# uno.net
KiCad netlist of a schematic drawn in EAGLE
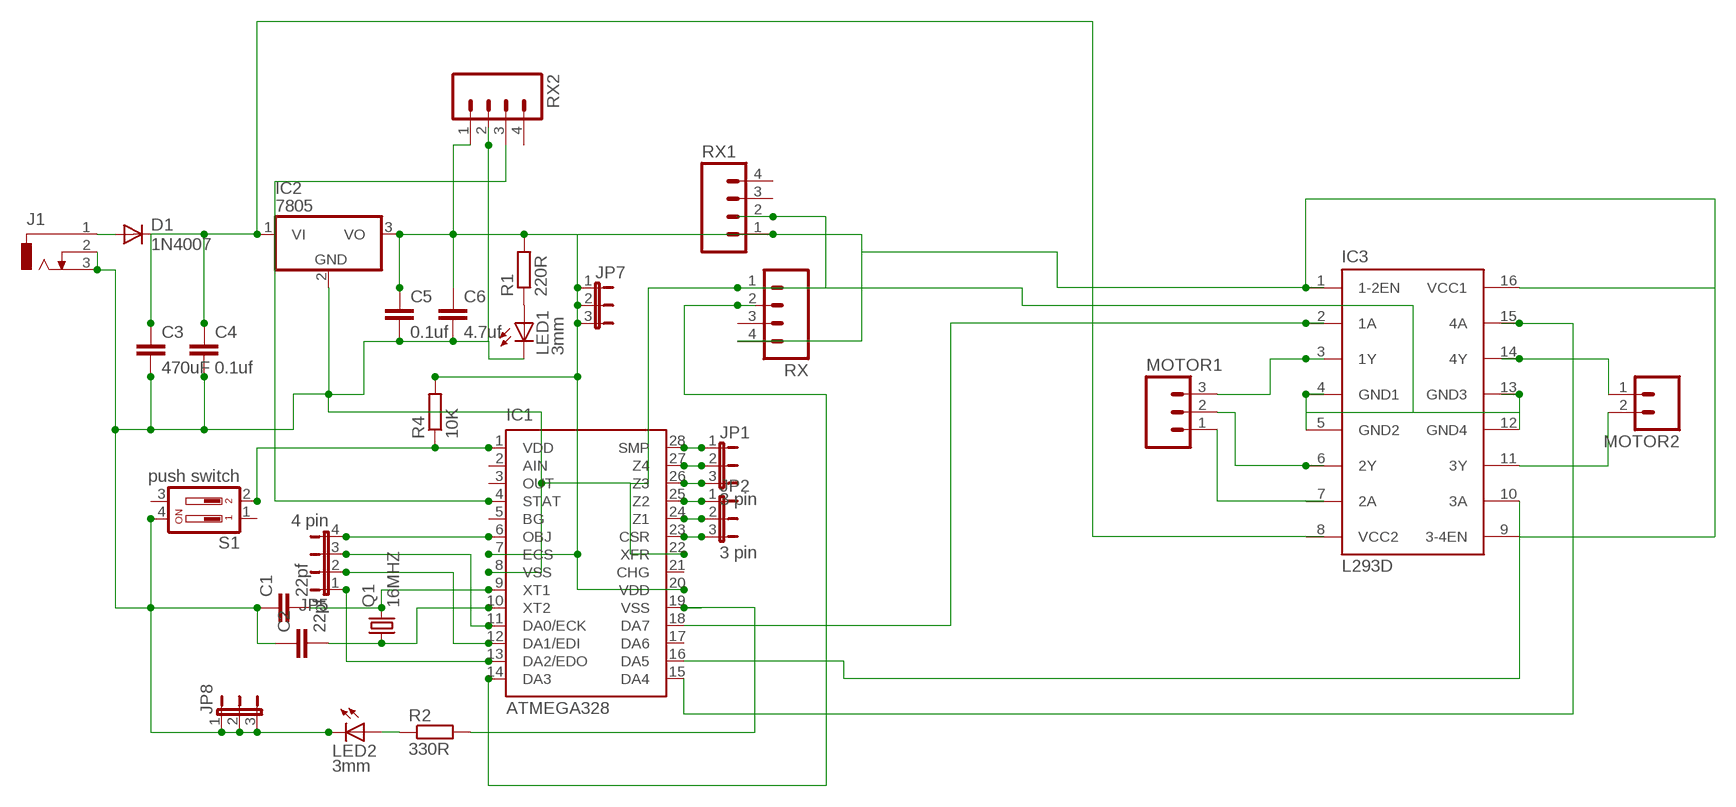
[diagram p0: schematic, sheet 1]

(export (version "E")
  (design (tool "Eeschema 10.0.6"))
  (components
    (comp (ref "C1")
      (value "22pf")
      (footprint "eagle-import:C2.5-2")
      (libsource (lib "eagle-import") (part "C2.5/2"))
    )
    (comp (ref "C2")
      (value "22pf")
      (footprint "eagle-import:C2.5-2")
      (libsource (lib "eagle-import") (part "C2.5/2"))
    )
    (comp (ref "C3")
      (value "470uF")
      (footprint "eagle-import:C2.5-2")
      (libsource (lib "eagle-import") (part "C2.5/2"))
    )
    (comp (ref "C4")
      (value "0.1uf")
      (footprint "eagle-import:C2.5-2")
      (libsource (lib "eagle-import") (part "C2.5/2"))
    )
    (comp (ref "C5")
      (value "0.1uf")
      (footprint "eagle-import:C2.5-2")
      (libsource (lib "eagle-import") (part "C2.5/2"))
    )
    (comp (ref "C6")
      (value "4.7uf")
      (footprint "eagle-import:C2.5-2")
      (libsource (lib "eagle-import") (part "C2.5/2"))
    )
    (comp (ref "D1")
      (value "1N4007")
      (footprint "eagle-import:DO41-10")
      (libsource (lib "eagle-import") (part "1N4004"))
    )
    (comp (ref "IC1")
      (value "ATMEGA328")
      (footprint "eagle-import:DIL28-3")
      (libsource (lib "eagle-import") (part "QT9701BD"))
    )
    (comp (ref "IC2")
      (value "7805")
      (footprint "eagle-import:TO220V")
      (libsource (lib "eagle-import") (part "78TV6"))
    )
    (comp (ref "IC3")
      (value "L293D")
      (footprint "eagle-import:DIL16")
      (libsource (lib "eagle-import") (part "L293D"))
    )
    (comp (ref "J1")
      (value "DCJ0303")
      (footprint "eagle-import:DCJ0303")
      (libsource (lib "eagle-import") (part "DCJ0303"))
    )
    (comp (ref "JP1")
      (value "3 pin")
      (footprint "eagle-import:JP2")
      (libsource (lib "eagle-import") (part "JP2E"))
    )
    (comp (ref "JP2")
      (value "3 pin")
      (footprint "eagle-import:JP2")
      (libsource (lib "eagle-import") (part "JP2E"))
    )
    (comp (ref "JP5")
      (value "4 pin")
      (footprint "eagle-import:JP4")
      (libsource (lib "eagle-import") (part "JP4E"))
    )
    (comp (ref "JP7")
      (value "JP2E")
      (footprint "eagle-import:JP2")
      (libsource (lib "eagle-import") (part "JP2E"))
    )
    (comp (ref "JP8")
      (value "JP2E")
      (footprint "eagle-import:JP2")
      (libsource (lib "eagle-import") (part "JP2E"))
    )
    (comp (ref "LED1")
      (value "3mm")
      (footprint "eagle-import:LED3MM")
      (libsource (lib "eagle-import") (part "LED3MM"))
    )
    (comp (ref "LED2")
      (value "3mm")
      (footprint "eagle-import:LED3MM")
      (libsource (lib "eagle-import") (part "LED3MM"))
    )
    (comp (ref "MOTOR1")
      (value "M03")
      (footprint "eagle-import:03P")
      (libsource (lib "eagle-import") (part "M03"))
    )
    (comp (ref "MOTOR2")
      (value "M02")
      (footprint "eagle-import:02P")
      (libsource (lib "eagle-import") (part "M02"))
    )
    (comp (ref "Q1")
      (value "16MHZ")
      (footprint "eagle-import:HC49_S")
      (libsource (lib "eagle-import") (part "CRYSTALHC49S"))
    )
    (comp (ref "R1")
      (value "220R")
      (footprint "eagle-import:0207_10")
      (libsource (lib "eagle-import") (part "R-EU_0207/10"))
    )
    (comp (ref "R2")
      (value "330R")
      (footprint "eagle-import:0207_10")
      (libsource (lib "eagle-import") (part "R-EU_0207/10"))
    )
    (comp (ref "R4")
      (value "10K")
      (footprint "eagle-import:0207_10")
      (libsource (lib "eagle-import") (part "R-EU_0207/10"))
    )
    (comp (ref "RX")
      (value "M04")
      (footprint "eagle-import:04P")
      (libsource (lib "eagle-import") (part "M04"))
    )
    (comp (ref "RX1")
      (value "M04")
      (footprint "eagle-import:04P")
      (fields (field (name "OC_FARNELL") "unknown") (field (name "OC_NEWARK") "unknown"))
      (libsource (lib "eagle-import") (part "M04"))
    )
    (comp (ref "RX2")
      (value "M04")
      (footprint "eagle-import:04P")
      (fields (field (name "OC_FARNELL") "unknown") (field (name "OC_NEWARK") "unknown"))
      (libsource (lib "eagle-import") (part "M04"))
    )
    (comp (ref "S1")
      (value "push switch")
      (footprint "eagle-import:DP-02")
      (fields (field (name "MPN") "MCDP02"))
      (libsource (lib "eagle-import") (part "DP02"))
    )
  )
  (nets
    (net (code "1") (name "Net-(D1-PadA)") (class "Default")
      (node (ref "D1") (pin "A") (pinfunction "A_A") (pintype "passive"))
      (node (ref "J1") (pin "1") (pinfunction "1_1") (pintype "passive"))
    )
    (net (code "2") (name "Net-(IC1-CSR)") (class "Default")
      (node (ref "IC1") (pin "23") (pinfunction "CSR_23") (pintype "output"))
      (node (ref "JP2") (pin "3") (pinfunction "3_3") (pintype "passive"))
    )
    (net (code "3") (name "Net-(IC1-DA0{slash}ECK)") (class "Default")
      (node (ref "IC1") (pin "11") (pinfunction "DA0/ECK_11") (pintype "output"))
      (node (ref "JP5") (pin "3") (pinfunction "3_3") (pintype "passive"))
    )
    (net (code "4") (name "Net-(IC1-DA1{slash}EDI)") (class "Default")
      (node (ref "IC1") (pin "12") (pinfunction "DA1/EDI_12") (pintype "output"))
      (node (ref "JP5") (pin "2") (pinfunction "2_2") (pintype "passive"))
    )
    (net (code "5") (name "Net-(IC1-DA2{slash}EDO)") (class "Default")
      (node (ref "IC1") (pin "13") (pinfunction "DA2/EDO_13") (pintype "output"))
      (node (ref "JP5") (pin "1") (pinfunction "1_1") (pintype "passive"))
    )
    (net (code "6") (name "Net-(IC1-DA3)") (class "Default")
      (node (ref "IC1") (pin "14") (pinfunction "DA3_14") (pintype "output"))
      (node (ref "RX") (pin "2") (pinfunction "2_2") (pintype "passive"))
    )
    (net (code "7") (name "Net-(IC1-DA4)") (class "Default")
      (node (ref "IC1") (pin "15") (pinfunction "DA4_15") (pintype "output"))
      (node (ref "IC3") (pin "15") (pinfunction "4A_15") (pintype "input"))
    )
    (net (code "8") (name "Net-(IC1-DA5)") (class "Default")
      (node (ref "IC1") (pin "16") (pinfunction "DA5_16") (pintype "output"))
      (node (ref "IC3") (pin "10") (pinfunction "3A_10") (pintype "input"))
    )
    (net (code "9") (name "Net-(IC1-DA7)") (class "Default")
      (node (ref "IC1") (pin "18") (pinfunction "DA7_18") (pintype "output"))
      (node (ref "IC3") (pin "2") (pinfunction "1A_2") (pintype "input"))
    )
    (net (code "10") (name "Net-(IC1-ECS)") (class "Default")
      (node (ref "C5") (pin "1") (pinfunction "1_1") (pintype "passive"))
      (node (ref "C6") (pin "1") (pinfunction "1_1") (pintype "passive"))
      (node (ref "IC1") (pin "20") (pinfunction "VDD_20") (pintype "input"))
      (node (ref "IC1") (pin "7") (pinfunction "ECS_7") (pintype "output"))
      (node (ref "IC2") (pin "3") (pinfunction "VO_3") (pintype "passive"))
      (node (ref "IC3") (pin "1") (pinfunction "1-2EN_1") (pintype "input"))
      (node (ref "IC3") (pin "16") (pinfunction "VCC1_16") (pintype "power_in"))
      (node (ref "IC3") (pin "9") (pinfunction "3-4EN_9") (pintype "input"))
      (node (ref "JP7") (pin "1") (pinfunction "1_1") (pintype "passive"))
      (node (ref "JP7") (pin "2") (pinfunction "2_2") (pintype "passive"))
      (node (ref "JP7") (pin "3") (pinfunction "3_3") (pintype "passive"))
      (node (ref "R1") (pin "2") (pinfunction "2_2") (pintype "passive"))
      (node (ref "R4") (pin "2") (pinfunction "2_2") (pintype "passive"))
      (node (ref "RX") (pin "4") (pinfunction "4_4") (pintype "passive"))
      (node (ref "RX1") (pin "1") (pinfunction "1_1") (pintype "passive"))
      (node (ref "RX2") (pin "1") (pinfunction "1_1") (pintype "passive"))
    )
    (net (code "11") (name "Net-(IC1-OBJ)") (class "Default")
      (node (ref "IC1") (pin "6") (pinfunction "OBJ_6") (pintype "input"))
      (node (ref "JP5") (pin "4") (pinfunction "4_4") (pintype "passive"))
    )
    (net (code "12") (name "Net-(IC1-SMP)") (class "Default")
      (node (ref "IC1") (pin "28") (pinfunction "SMP_28") (pintype "output"))
      (node (ref "JP1") (pin "1") (pinfunction "1_1") (pintype "passive"))
    )
    (net (code "13") (name "Net-(IC1-STAT)") (class "Default")
      (node (ref "IC1") (pin "4") (pinfunction "STAT_4") (pintype "output"))
      (node (ref "RX2") (pin "3") (pinfunction "3_3") (pintype "passive"))
    )
    (net (code "14") (name "Net-(IC1-VDD-Pad1)") (class "Default")
      (node (ref "IC1") (pin "1") (pinfunction "VDD_1") (pintype "input"))
      (node (ref "R4") (pin "1") (pinfunction "1_1") (pintype "passive"))
      (node (ref "S1") (pin "2") (pinfunction "2_2") (pintype "passive"))
    )
    (net (code "15") (name "Net-(IC1-VSS-Pad19)") (class "Default")
      (node (ref "IC1") (pin "19") (pinfunction "VSS_19") (pintype "input"))
      (node (ref "R2") (pin "2") (pinfunction "2_2") (pintype "passive"))
    )
    (net (code "16") (name "Net-(IC1-XFR)") (class "Default")
      (node (ref "C1") (pin "1") (pinfunction "1_1") (pintype "passive"))
      (node (ref "C2") (pin "1") (pinfunction "1_1") (pintype "passive"))
      (node (ref "C3") (pin "2") (pinfunction "2_2") (pintype "passive"))
      (node (ref "C4") (pin "2") (pinfunction "2_2") (pintype "passive"))
      (node (ref "C5") (pin "2") (pinfunction "2_2") (pintype "passive"))
      (node (ref "C6") (pin "2") (pinfunction "2_2") (pintype "passive"))
      (node (ref "IC1") (pin "22") (pinfunction "XFR_22") (pintype "output"))
      (node (ref "IC1") (pin "8") (pinfunction "VSS_8") (pintype "input"))
      (node (ref "IC2") (pin "2") (pinfunction "GND_2") (pintype "passive"))
      (node (ref "IC3") (pin "12") (pinfunction "GND4_12") (pintype "power_in"))
      (node (ref "IC3") (pin "13") (pinfunction "GND3_13") (pintype "power_in"))
      (node (ref "IC3") (pin "4") (pinfunction "GND1_4") (pintype "power_in"))
      (node (ref "IC3") (pin "5") (pinfunction "GND2_5") (pintype "power_in"))
      (node (ref "J1") (pin "2") (pinfunction "2_2") (pintype "passive"))
      (node (ref "J1") (pin "3") (pinfunction "3_3") (pintype "passive"))
      (node (ref "JP8") (pin "1") (pinfunction "1_1") (pintype "passive"))
      (node (ref "JP8") (pin "2") (pinfunction "2_2") (pintype "passive"))
      (node (ref "JP8") (pin "3") (pinfunction "3_3") (pintype "passive"))
      (node (ref "LED1") (pin "K") (pinfunction "C_K") (pintype "passive"))
      (node (ref "LED2") (pin "K") (pinfunction "C_K") (pintype "passive"))
      (node (ref "RX") (pin "1") (pinfunction "1_1") (pintype "passive"))
      (node (ref "RX1") (pin "2") (pinfunction "2_2") (pintype "passive"))
      (node (ref "RX2") (pin "2") (pinfunction "2_2") (pintype "passive"))
      (node (ref "S1") (pin "4") (pinfunction "4_4") (pintype "passive"))
    )
    (net (code "17") (name "Net-(IC1-XT1)") (class "Default")
      (node (ref "C1") (pin "2") (pinfunction "2_2") (pintype "passive"))
      (node (ref "IC1") (pin "9") (pinfunction "XT1_9") (pintype "input"))
      (node (ref "Q1") (pin "2") (pinfunction "2_2") (pintype "passive"))
    )
    (net (code "18") (name "Net-(IC1-XT2)") (class "Default")
      (node (ref "C2") (pin "2") (pinfunction "2_2") (pintype "passive"))
      (node (ref "IC1") (pin "10") (pinfunction "XT2_10") (pintype "output"))
      (node (ref "Q1") (pin "1") (pinfunction "1_1") (pintype "passive"))
    )
    (net (code "19") (name "Net-(IC1-Z1)") (class "Default")
      (node (ref "IC1") (pin "24") (pinfunction "Z1_24") (pintype "output"))
      (node (ref "JP2") (pin "2") (pinfunction "2_2") (pintype "passive"))
    )
    (net (code "20") (name "Net-(IC1-Z2)") (class "Default")
      (node (ref "IC1") (pin "25") (pinfunction "Z2_25") (pintype "output"))
      (node (ref "JP2") (pin "1") (pinfunction "1_1") (pintype "passive"))
    )
    (net (code "21") (name "Net-(IC1-Z3)") (class "Default")
      (node (ref "IC1") (pin "26") (pinfunction "Z3_26") (pintype "output"))
      (node (ref "JP1") (pin "3") (pinfunction "3_3") (pintype "passive"))
    )
    (net (code "22") (name "Net-(IC1-Z4)") (class "Default")
      (node (ref "IC1") (pin "27") (pinfunction "Z4_27") (pintype "output"))
      (node (ref "JP1") (pin "2") (pinfunction "2_2") (pintype "passive"))
    )
    (net (code "23") (name "Net-(IC2-VI)") (class "Default")
      (node (ref "C3") (pin "1") (pinfunction "1_1") (pintype "passive"))
      (node (ref "C4") (pin "1") (pinfunction "1_1") (pintype "passive"))
      (node (ref "D1") (pin "C") (pinfunction "C_C") (pintype "passive"))
      (node (ref "IC2") (pin "1") (pinfunction "VI_1") (pintype "input"))
      (node (ref "IC3") (pin "8") (pinfunction "VCC2_8") (pintype "power_in"))
    )
    (net (code "24") (name "Net-(IC3-1Y)") (class "Default")
      (node (ref "IC3") (pin "3") (pinfunction "1Y_3") (pintype "output"))
      (node (ref "MOTOR1") (pin "3") (pinfunction "3_3") (pintype "passive"))
    )
    (net (code "25") (name "Net-(IC3-2A)") (class "Default")
      (node (ref "IC3") (pin "7") (pinfunction "2A_7") (pintype "input"))
      (node (ref "MOTOR1") (pin "1") (pinfunction "1_1") (pintype "passive"))
    )
    (net (code "26") (name "Net-(IC3-2Y)") (class "Default")
      (node (ref "IC3") (pin "6") (pinfunction "2Y_6") (pintype "output"))
      (node (ref "MOTOR1") (pin "2") (pinfunction "2_2") (pintype "passive"))
    )
    (net (code "27") (name "Net-(IC3-3Y)") (class "Default")
      (node (ref "IC3") (pin "11") (pinfunction "3Y_11") (pintype "output"))
      (node (ref "MOTOR2") (pin "2") (pinfunction "2_2") (pintype "passive"))
    )
    (net (code "28") (name "Net-(IC3-4Y)") (class "Default")
      (node (ref "IC3") (pin "14") (pinfunction "4Y_14") (pintype "output"))
      (node (ref "MOTOR2") (pin "1") (pinfunction "1_1") (pintype "passive"))
    )
    (net (code "29") (name "Net-(LED1-PadA)") (class "Default")
      (node (ref "LED1") (pin "A") (pinfunction "A_A") (pintype "passive"))
      (node (ref "R1") (pin "1") (pinfunction "1_1") (pintype "passive"))
    )
    (net (code "30") (name "Net-(LED2-PadA)") (class "Default")
      (node (ref "LED2") (pin "A") (pinfunction "A_A") (pintype "passive"))
      (node (ref "R2") (pin "1") (pinfunction "1_1") (pintype "passive"))
    )
    (net (code "31") (name "unconnected-(IC1-AIN-Pad2)") (class "Default")
      (node (ref "IC1") (pin "2") (pinfunction "AIN_2") (pintype "input"))
    )
    (net (code "32") (name "unconnected-(IC1-BG-Pad5)") (class "Default")
      (node (ref "IC1") (pin "5") (pinfunction "BG_5") (pintype "input"))
    )
    (net (code "33") (name "unconnected-(IC1-CHG-Pad21)") (class "Default")
      (node (ref "IC1") (pin "21") (pinfunction "CHG_21") (pintype "output"))
    )
    (net (code "34") (name "unconnected-(IC1-DA6-Pad17)") (class "Default")
      (node (ref "IC1") (pin "17") (pinfunction "DA6_17") (pintype "output"))
    )
    (net (code "35") (name "unconnected-(IC1-OUT-Pad3)") (class "Default")
      (node (ref "IC1") (pin "3") (pinfunction "OUT_3") (pintype "output"))
    )
    (net (code "36") (name "unconnected-(RX-Pad3)") (class "Default")
      (node (ref "RX") (pin "3") (pinfunction "3_3") (pintype "passive"))
    )
    (net (code "37") (name "unconnected-(RX1-Pad3)") (class "Default")
      (node (ref "RX1") (pin "3") (pinfunction "3_3") (pintype "passive"))
    )
    (net (code "38") (name "unconnected-(RX1-Pad4)") (class "Default")
      (node (ref "RX1") (pin "4") (pinfunction "4_4") (pintype "passive"))
    )
    (net (code "39") (name "unconnected-(RX2-Pad4)") (class "Default")
      (node (ref "RX2") (pin "4") (pinfunction "4_4") (pintype "passive"))
    )
    (net (code "40") (name "unconnected-(S1-Pad1)") (class "Default")
      (node (ref "S1") (pin "1") (pinfunction "1_1") (pintype "passive"))
    )
    (net (code "41") (name "unconnected-(S1-Pad3)") (class "Default")
      (node (ref "S1") (pin "3") (pinfunction "3_3") (pintype "passive"))
    )
  )
)
